# USB_HUB_4_Port.net
KiCad netlist of a schematic drawn in Altium Designer
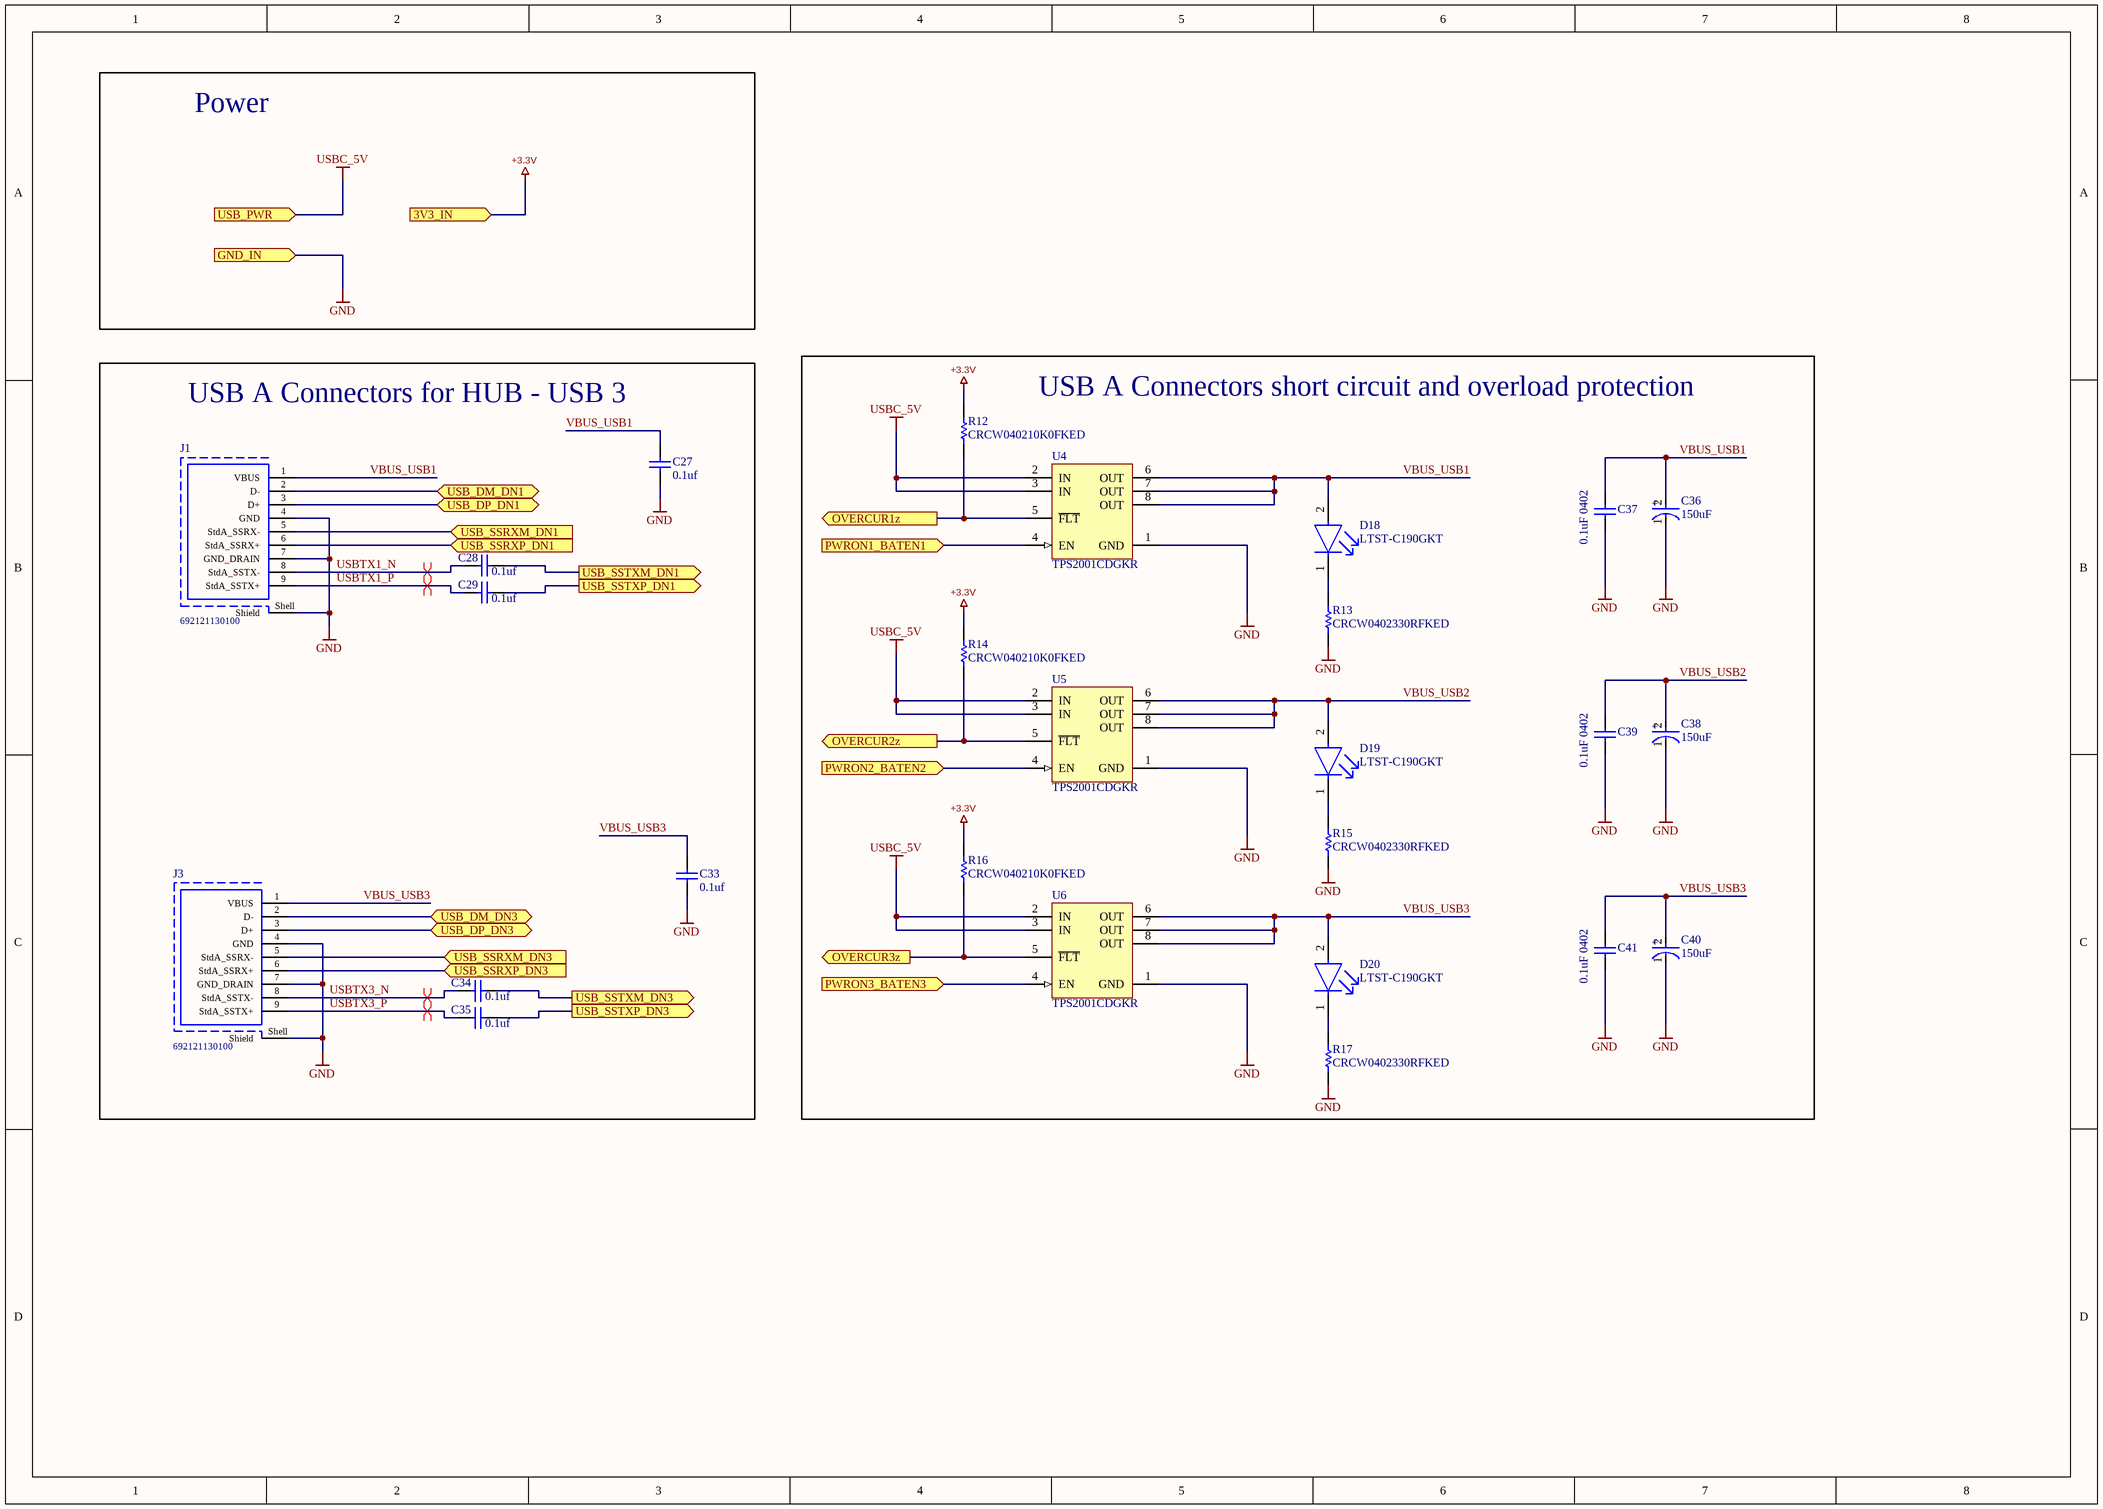
[diagram p0: USB_HUB_4 Port.SchDoc]

(export (version "E")
  (design (tool "Eeschema 10.0.6"))
  (components
    (comp (ref "C27")
      (value "0.1uf")
      (footprint "CAPC1005X55X30ML05T10")
      (fields (field (name "MANUFACTURER") "Kemet") (field (name "PART NUMBER") "C0402C104J4RACTU"))
      (libsource (lib "Altium Content Vault") (part "CAP"))
    )
    (comp (ref "C28")
      (value "0.1uf")
      (footprint "CAPC1005X55X30ML05T10")
      (fields (field (name "MANUFACTURER") "Kemet") (field (name "PART NUMBER") "C0402C104J4RACTU"))
      (libsource (lib "Altium Content Vault") (part "CAP"))
    )
    (comp (ref "C29")
      (value "0.1uf")
      (footprint "CAPC1005X55X30ML05T10")
      (fields (field (name "MANUFACTURER") "Kemet") (field (name "PART NUMBER") "C0402C104J4RACTU"))
      (libsource (lib "Altium Content Vault") (part "CAP"))
    )
    (comp (ref "C33")
      (value "0.1uf")
      (footprint "CAPC1005X55X30ML05T10")
      (fields (field (name "MANUFACTURER") "Kemet") (field (name "PART NUMBER") "C0402C104J4RACTU"))
      (libsource (lib "Altium Content Vault") (part "CAP"))
    )
    (comp (ref "C34")
      (value "0.1uf")
      (footprint "CAPC1005X55X30ML05T10")
      (fields (field (name "MANUFACTURER") "Kemet") (field (name "PART NUMBER") "C0402C104J4RACTU"))
      (libsource (lib "Altium Content Vault") (part "CAP"))
    )
    (comp (ref "C35")
      (value "0.1uf")
      (footprint "CAPC1005X55X30ML05T10")
      (fields (field (name "MANUFACTURER") "Kemet") (field (name "PART NUMBER") "C0402C104J4RACTU"))
      (libsource (lib "Altium Content Vault") (part "CAP"))
    )
    (comp (ref "C36")
      (value "150uF")
      (footprint "FP-SVPEB6-MFG")
      (description "CAP ALUM POLY 150UF 20% 6.3V SMD")
      (fields (field (name "TOLERANCE") "20%") (field (name "VOLTAGE") "6.3V"))
      (libsource (lib "Altium Content Vault") (part "203bc49f2ac43e59fd269a8c329ed05"))
    )
    (comp (ref "C37")
      (value "0.1uF 0402")
      (footprint "CAPC1005X55X30ML05T10")
      (fields (field (name "MANUFACTURER") "Kemet") (field (name "PART NUMBER") "C0402C104J4RACTU"))
      (libsource (lib "Altium Content Vault") (part "CAP"))
    )
    (comp (ref "C38")
      (value "150uF")
      (footprint "FP-SVPEB6-MFG")
      (description "CAP ALUM POLY 150UF 20% 6.3V SMD")
      (fields (field (name "TOLERANCE") "20%") (field (name "VOLTAGE") "6.3V"))
      (libsource (lib "Altium Content Vault") (part "203bc49f2ac43e59fd269a8c329ed05"))
    )
    (comp (ref "C39")
      (value "0.1uF 0402")
      (footprint "CAPC1005X55X30ML05T10")
      (fields (field (name "MANUFACTURER") "Kemet") (field (name "PART NUMBER") "C0402C104J4RACTU"))
      (libsource (lib "Altium Content Vault") (part "CAP"))
    )
    (comp (ref "C40")
      (value "150uF")
      (footprint "FP-SVPEB6-MFG")
      (description "CAP ALUM POLY 150UF 20% 6.3V SMD")
      (fields (field (name "TOLERANCE") "20%") (field (name "VOLTAGE") "6.3V"))
      (libsource (lib "Altium Content Vault") (part "203bc49f2ac43e59fd269a8c329ed05"))
    )
    (comp (ref "C41")
      (value "0.1uF 0402")
      (footprint "CAPC1005X55X30ML05T10")
      (fields (field (name "MANUFACTURER") "Kemet") (field (name "PART NUMBER") "C0402C104J4RACTU"))
      (libsource (lib "Altium Content Vault") (part "CAP"))
    )
    (comp (ref "D18")
      (value "LTST-C190GKT")
      (footprint "FP-LTST-C190GKT-MFG")
      (description "LED GREEN CLEAR CHIP SMD")
      (fields (field (name "VOLTAGE") "2V"))
      (libsource (lib "Altium Content Vault") (part "8706943c75ba83719d021d2fdc84c58"))
    )
    (comp (ref "D19")
      (value "LTST-C190GKT")
      (footprint "FP-LTST-C190GKT-MFG")
      (description "LED GREEN CLEAR CHIP SMD")
      (fields (field (name "VOLTAGE") "2V"))
      (libsource (lib "Altium Content Vault") (part "8706943c75ba83719d021d2fdc84c58"))
    )
    (comp (ref "D20")
      (value "LTST-C190GKT")
      (footprint "FP-LTST-C190GKT-MFG")
      (description "LED GREEN CLEAR CHIP SMD")
      (fields (field (name "VOLTAGE") "2V"))
      (libsource (lib "Altium Content Vault") (part "8706943c75ba83719d021d2fdc84c58"))
    )
    (comp (ref "J1")
      (value "692121130100")
      (footprint "692121130100")
      (description "USB 3.0 Type A Receptacle WR-COM, Reverse Horizontal, SMT / THT, with Clips, with 0.14 mm Offset")
      (fields (field (name "MANUFACTURER") "Wurth Elektronik") (field (name "PUBLISHER") "WurthElektronik"))
      (libsource (lib "Altium Content Vault") (part "WE-USB-9-1SHLD"))
    )
    (comp (ref "J3")
      (value "692121130100")
      (footprint "692121130100")
      (description "USB 3.0 Type A Receptacle WR-COM, Reverse Horizontal, SMT / THT, with Clips, with 0.14 mm Offset")
      (fields (field (name "MANUFACTURER") "Wurth Elektronik") (field (name "PUBLISHER") "WurthElektronik"))
      (libsource (lib "Altium Content Vault") (part "WE-USB-9-1SHLD"))
    )
    (comp (ref "R12")
      (value "CRCW040210K0FKED")
      (footprint "RESC1005X40X25NL05T05")
      (fields (field (name "MANUFACTURER") "Vishay Dale"))
      (libsource (lib "Altium Content Vault") (part "RES"))
    )
    (comp (ref "R13")
      (value "CRCW0402330RFKED")
      (footprint "RESC1005X40X25NL05T05")
      (fields (field (name "MANUFACTURER") "Vishay Dale"))
      (libsource (lib "Altium Content Vault") (part "RES"))
    )
    (comp (ref "R14")
      (value "CRCW040210K0FKED")
      (footprint "RESC1005X40X25NL05T05")
      (fields (field (name "MANUFACTURER") "Vishay Dale"))
      (libsource (lib "Altium Content Vault") (part "RES"))
    )
    (comp (ref "R15")
      (value "CRCW0402330RFKED")
      (footprint "RESC1005X40X25NL05T05")
      (fields (field (name "MANUFACTURER") "Vishay Dale"))
      (libsource (lib "Altium Content Vault") (part "RES"))
    )
    (comp (ref "R16")
      (value "CRCW040210K0FKED")
      (footprint "RESC1005X40X25NL05T05")
      (fields (field (name "MANUFACTURER") "Vishay Dale"))
      (libsource (lib "Altium Content Vault") (part "RES"))
    )
    (comp (ref "R17")
      (value "CRCW0402330RFKED")
      (footprint "RESC1005X40X25NL05T05")
      (fields (field (name "MANUFACTURER") "Vishay Dale"))
      (libsource (lib "Altium Content Vault") (part "RES"))
    )
    (comp (ref "U4")
      (value "TPS2001CDGKR")
      (footprint "DGK0008A_L")
      (fields (field (name "MANUFACTURER") "Texas Instruments"))
      (libsource (lib "Altium Content Vault") (part "TI-TPS2001CDGK8"))
    )
    (comp (ref "U5")
      (value "TPS2001CDGKR")
      (footprint "DGK0008A_L")
      (fields (field (name "MANUFACTURER") "Texas Instruments"))
      (libsource (lib "Altium Content Vault") (part "TI-TPS2001CDGK8"))
    )
    (comp (ref "U6")
      (value "TPS2001CDGKR")
      (footprint "DGK0008A_L")
      (fields (field (name "MANUFACTURER") "Texas Instruments"))
      (libsource (lib "Altium Content Vault") (part "TI-TPS2001CDGK8"))
    )
  )
  (nets
    (net (code "1") (name "+3.3V") (class "Default")
      (node (ref "R12") (pin "2") (pinfunction "2_2") (pintype "passive"))
      (node (ref "R14") (pin "2") (pinfunction "2_2") (pintype "passive"))
      (node (ref "R16") (pin "2") (pinfunction "2_2") (pintype "passive"))
    )
    (net (code "2") (name "/OVERCUR1z") (class "Default")
      (node (ref "R12") (pin "1") (pinfunction "1_1") (pintype "passive"))
      (node (ref "U4") (pin "5") (pinfunction "~{FLT}_5") (pintype "tri_state"))
    )
    (net (code "3") (name "/OVERCUR2z") (class "Default")
      (node (ref "R14") (pin "1") (pinfunction "1_1") (pintype "passive"))
      (node (ref "U5") (pin "5") (pinfunction "~{FLT}_5") (pintype "tri_state"))
    )
    (net (code "4") (name "/OVERCUR3z") (class "Default")
      (node (ref "R16") (pin "1") (pinfunction "1_1") (pintype "passive"))
      (node (ref "U6") (pin "5") (pinfunction "~{FLT}_5") (pintype "tri_state"))
    )
    (net (code "5") (name "/PWRON1_BATEN1") (class "Default")
      (node (ref "U4") (pin "4") (pinfunction "EN_4") (pintype "input"))
    )
    (net (code "6") (name "/PWRON2_BATEN2") (class "Default")
      (node (ref "U5") (pin "4") (pinfunction "EN_4") (pintype "input"))
    )
    (net (code "7") (name "/PWRON3_BATEN3") (class "Default")
      (node (ref "U6") (pin "4") (pinfunction "EN_4") (pintype "input"))
    )
    (net (code "8") (name "/USBTX1_N") (class "Default")
      (node (ref "C28") (pin "1") (pinfunction "1_1") (pintype "passive"))
      (node (ref "J1") (pin "8") (pinfunction "StdA_SSTX-_8") (pintype "passive"))
    )
    (net (code "9") (name "/USBTX1_P") (class "Default")
      (node (ref "C29") (pin "1") (pinfunction "1_1") (pintype "passive"))
      (node (ref "J1") (pin "9") (pinfunction "StdA_SSTX+_9") (pintype "passive"))
    )
    (net (code "10") (name "/USBTX3_N") (class "Default")
      (node (ref "C34") (pin "1") (pinfunction "1_1") (pintype "passive"))
      (node (ref "J3") (pin "8") (pinfunction "StdA_SSTX-_8") (pintype "passive"))
    )
    (net (code "11") (name "/USBTX3_P") (class "Default")
      (node (ref "C35") (pin "1") (pinfunction "1_1") (pintype "passive"))
      (node (ref "J3") (pin "9") (pinfunction "StdA_SSTX+_9") (pintype "passive"))
    )
    (net (code "12") (name "/USB_DM_DN1") (class "Default")
      (node (ref "J1") (pin "2") (pinfunction "D-_2") (pintype "passive"))
    )
    (net (code "13") (name "/USB_DM_DN3") (class "Default")
      (node (ref "J3") (pin "2") (pinfunction "D-_2") (pintype "passive"))
    )
    (net (code "14") (name "/USB_DP_DN1") (class "Default")
      (node (ref "J1") (pin "3") (pinfunction "D+_3") (pintype "passive"))
    )
    (net (code "15") (name "/USB_DP_DN3") (class "Default")
      (node (ref "J3") (pin "3") (pinfunction "D+_3") (pintype "passive"))
    )
    (net (code "16") (name "/USB_SSRXM_DN1") (class "Default")
      (node (ref "J1") (pin "5") (pinfunction "StdA_SSRX-_5") (pintype "passive"))
    )
    (net (code "17") (name "/USB_SSRXM_DN3") (class "Default")
      (node (ref "J3") (pin "5") (pinfunction "StdA_SSRX-_5") (pintype "passive"))
    )
    (net (code "18") (name "/USB_SSRXP_DN1") (class "Default")
      (node (ref "J1") (pin "6") (pinfunction "StdA_SSRX+_6") (pintype "passive"))
    )
    (net (code "19") (name "/USB_SSRXP_DN3") (class "Default")
      (node (ref "J3") (pin "6") (pinfunction "StdA_SSRX+_6") (pintype "passive"))
    )
    (net (code "20") (name "/USB_SSTXM_DN1") (class "Default")
      (node (ref "C28") (pin "2") (pinfunction "2_2") (pintype "passive"))
    )
    (net (code "21") (name "/USB_SSTXM_DN3") (class "Default")
      (node (ref "C34") (pin "2") (pinfunction "2_2") (pintype "passive"))
    )
    (net (code "22") (name "/USB_SSTXP_DN1") (class "Default")
      (node (ref "C29") (pin "2") (pinfunction "2_2") (pintype "passive"))
    )
    (net (code "23") (name "/USB_SSTXP_DN3") (class "Default")
      (node (ref "C35") (pin "2") (pinfunction "2_2") (pintype "passive"))
    )
    (net (code "24") (name "/VBUS_USB1") (class "Default")
      (node (ref "C27") (pin "2") (pinfunction "2_2") (pintype "passive"))
      (node (ref "C36") (pin "2") (pinfunction "A_2") (pintype "passive"))
      (node (ref "C37") (pin "2") (pinfunction "2_2") (pintype "passive"))
      (node (ref "D18") (pin "2") (pinfunction "A_2") (pintype "passive"))
      (node (ref "J1") (pin "1") (pinfunction "VBUS_1") (pintype "passive"))
      (node (ref "U4") (pin "6") (pinfunction "OUT_6") (pintype "power_in"))
      (node (ref "U4") (pin "7") (pinfunction "OUT_7") (pintype "power_in"))
      (node (ref "U4") (pin "8") (pinfunction "OUT_8") (pintype "power_in"))
    )
    (net (code "25") (name "/VBUS_USB2") (class "Default")
      (node (ref "C38") (pin "2") (pinfunction "A_2") (pintype "passive"))
      (node (ref "C39") (pin "2") (pinfunction "2_2") (pintype "passive"))
      (node (ref "D19") (pin "2") (pinfunction "A_2") (pintype "passive"))
      (node (ref "U5") (pin "6") (pinfunction "OUT_6") (pintype "power_in"))
      (node (ref "U5") (pin "7") (pinfunction "OUT_7") (pintype "power_in"))
      (node (ref "U5") (pin "8") (pinfunction "OUT_8") (pintype "power_in"))
    )
    (net (code "26") (name "/VBUS_USB3") (class "Default")
      (node (ref "C33") (pin "2") (pinfunction "2_2") (pintype "passive"))
      (node (ref "C40") (pin "2") (pinfunction "A_2") (pintype "passive"))
      (node (ref "C41") (pin "2") (pinfunction "2_2") (pintype "passive"))
      (node (ref "D20") (pin "2") (pinfunction "A_2") (pintype "passive"))
      (node (ref "J3") (pin "1") (pinfunction "VBUS_1") (pintype "passive"))
      (node (ref "U6") (pin "6") (pinfunction "OUT_6") (pintype "power_in"))
      (node (ref "U6") (pin "7") (pinfunction "OUT_7") (pintype "power_in"))
      (node (ref "U6") (pin "8") (pinfunction "OUT_8") (pintype "power_in"))
    )
    (net (code "27") (name "GND") (class "Default")
      (node (ref "C27") (pin "1") (pinfunction "1_1") (pintype "passive"))
      (node (ref "C33") (pin "1") (pinfunction "1_1") (pintype "passive"))
      (node (ref "C36") (pin "1") (pinfunction "C_1") (pintype "passive"))
      (node (ref "C37") (pin "1") (pinfunction "1_1") (pintype "passive"))
      (node (ref "C38") (pin "1") (pinfunction "C_1") (pintype "passive"))
      (node (ref "C39") (pin "1") (pinfunction "1_1") (pintype "passive"))
      (node (ref "C40") (pin "1") (pinfunction "C_1") (pintype "passive"))
      (node (ref "C41") (pin "1") (pinfunction "1_1") (pintype "passive"))
      (node (ref "J1") (pin "4") (pinfunction "GND_4") (pintype "passive"))
      (node (ref "J1") (pin "7") (pinfunction "GND_DRAIN_7") (pintype "passive"))
      (node (ref "J1") (pin "Shell") (pinfunction "Shield_Shell") (pintype "passive"))
      (node (ref "J3") (pin "4") (pinfunction "GND_4") (pintype "passive"))
      (node (ref "J3") (pin "7") (pinfunction "GND_DRAIN_7") (pintype "passive"))
      (node (ref "J3") (pin "Shell") (pinfunction "Shield_Shell") (pintype "passive"))
      (node (ref "R13") (pin "1") (pinfunction "1_1") (pintype "passive"))
      (node (ref "R15") (pin "1") (pinfunction "1_1") (pintype "passive"))
      (node (ref "R17") (pin "1") (pinfunction "1_1") (pintype "passive"))
      (node (ref "U4") (pin "1") (pinfunction "GND_1") (pintype "power_in"))
      (node (ref "U5") (pin "1") (pinfunction "GND_1") (pintype "power_in"))
      (node (ref "U6") (pin "1") (pinfunction "GND_1") (pintype "power_in"))
    )
    (net (code "28") (name "Net-(D18-C)") (class "Default")
      (node (ref "D18") (pin "1") (pinfunction "C_1") (pintype "passive"))
      (node (ref "R13") (pin "2") (pinfunction "2_2") (pintype "passive"))
    )
    (net (code "29") (name "Net-(D19-C)") (class "Default")
      (node (ref "D19") (pin "1") (pinfunction "C_1") (pintype "passive"))
      (node (ref "R15") (pin "2") (pinfunction "2_2") (pintype "passive"))
    )
    (net (code "30") (name "Net-(D20-C)") (class "Default")
      (node (ref "D20") (pin "1") (pinfunction "C_1") (pintype "passive"))
      (node (ref "R17") (pin "2") (pinfunction "2_2") (pintype "passive"))
    )
    (net (code "31") (name "USBC_5V") (class "Default")
      (node (ref "U4") (pin "2") (pinfunction "IN_2") (pintype "power_in"))
      (node (ref "U4") (pin "3") (pinfunction "IN_3") (pintype "power_in"))
      (node (ref "U5") (pin "2") (pinfunction "IN_2") (pintype "power_in"))
      (node (ref "U5") (pin "3") (pinfunction "IN_3") (pintype "power_in"))
      (node (ref "U6") (pin "2") (pinfunction "IN_2") (pintype "power_in"))
      (node (ref "U6") (pin "3") (pinfunction "IN_3") (pintype "power_in"))
    )
  )
)
